# ReadCard.net
KiCad netlist of a schematic drawn in Altium Designer
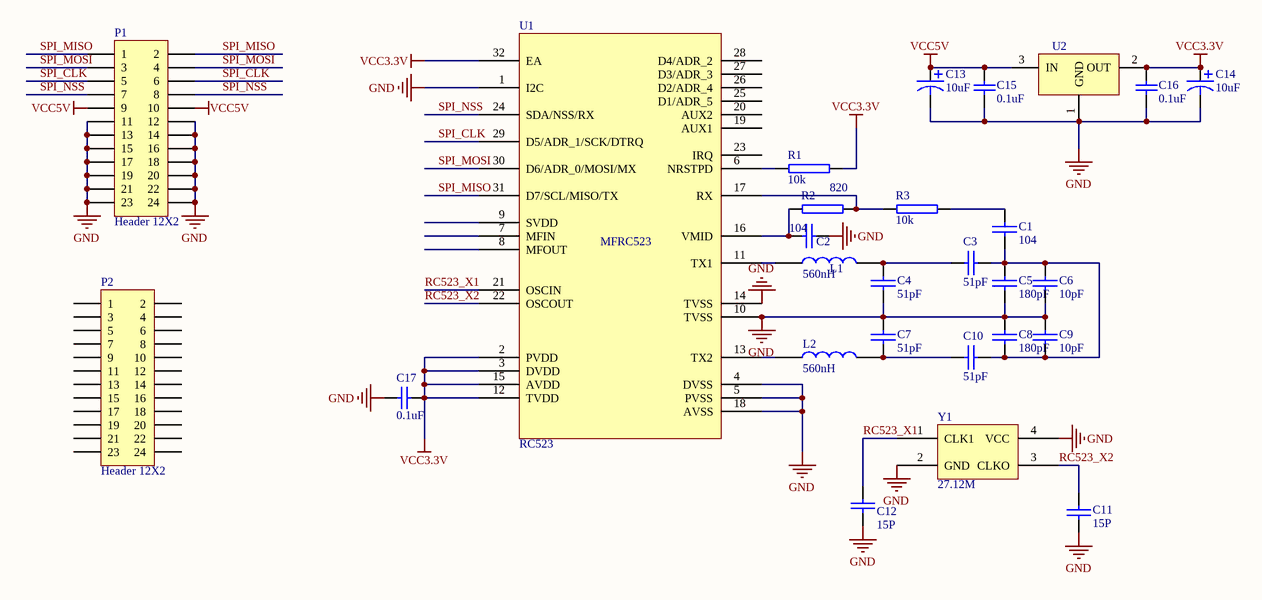
[diagram p0: ReadCard.SchDoc]

(export (version "E")
  (design (tool "Eeschema 10.0.6"))
  (components
    (comp (ref "C1")
      (value "104")
      (footprint "0603C")
      (description "Capacitor")
      (libsource (lib "*") (part "CAP"))
    )
    (comp (ref "C2")
      (value "104")
      (footprint "0603C")
      (description "Capacitor")
      (libsource (lib "*") (part "CAP"))
    )
    (comp (ref "C3")
      (value "51pF")
      (footprint "0603C")
      (description "Capacitor")
      (libsource (lib "*") (part "CAP"))
    )
    (comp (ref "C4")
      (value "51pF")
      (footprint "0603C")
      (description "Capacitor")
      (libsource (lib "*") (part "CAP"))
    )
    (comp (ref "C5")
      (value "180pF")
      (footprint "0603C")
      (description "Capacitor")
      (libsource (lib "*") (part "CAP"))
    )
    (comp (ref "C6")
      (value "10pF")
      (footprint "0603C")
      (description "Capacitor")
      (libsource (lib "*") (part "CAP"))
    )
    (comp (ref "C7")
      (value "51pF")
      (footprint "0603C")
      (description "Capacitor")
      (libsource (lib "*") (part "CAP"))
    )
    (comp (ref "C8")
      (value "180pF")
      (footprint "0603C")
      (description "Capacitor")
      (libsource (lib "*") (part "CAP"))
    )
    (comp (ref "C9")
      (value "10pF")
      (footprint "0603C")
      (description "Capacitor")
      (libsource (lib "*") (part "CAP"))
    )
    (comp (ref "C10")
      (value "51pF")
      (footprint "0603C")
      (description "Capacitor")
      (libsource (lib "*") (part "CAP"))
    )
    (comp (ref "C11")
      (value "15P")
      (footprint "0603c")
      (description "Capacitor")
      (libsource (lib "") (part "CAP_1"))
    )
    (comp (ref "C12")
      (value "15P")
      (footprint "0603C")
      (description "Capacitor")
      (libsource (lib "") (part "CAP_1"))
    )
    (comp (ref "C13")
      (value "10uF")
      (footprint "1206_C")
      (description "贴片电容，1206")
      (libsource (lib "MES-terminal") (part "CAPACITOR"))
    )
    (comp (ref "C14")
      (value "10uF")
      (footprint "1206_C")
      (description "贴片电容，1206")
      (libsource (lib "MES-terminal") (part "CAPACITOR"))
    )
    (comp (ref "C15")
      (value "0.1uF")
      (footprint "0603_C")
      (description "贴片电容，0603")
      (libsource (lib "stm8l052r8t6开发板") (part "Cap"))
    )
    (comp (ref "C16")
      (value "0.1uF")
      (footprint "0603_C")
      (description "贴片电容，0603")
      (libsource (lib "stm8l052r8t6开发板") (part "Cap"))
    )
    (comp (ref "C17")
      (value "0.1uF")
      (footprint "0603_C")
      (description "贴片电容，0603")
      (libsource (lib "stm8l052r8t6开发板") (part "Cap"))
    )
    (comp (ref "L1") (value "560nH") (footprint "0805r") (libsource (lib "*") (part "INDUCTOR1")))
    (comp (ref "L2") (value "560nH") (footprint "0805r") (libsource (lib "*") (part "INDUCTOR1")))
    (comp (ref "P1")
      (value "Header 12X2")
      (footprint "12x2_2.0mm")
      (description "Header, 12-Pin, Dual row, 2.0mm")
      (libsource (lib "Miscellaneous Connectors") (part "Header 12X2"))
    )
    (comp (ref "P2")
      (value "Header 12X2")
      (footprint "12x2_2.0mm")
      (description "Header, 12-Pin, Dual row, 2.0mm")
      (libsource (lib "Miscellaneous Connectors") (part "Header 12X2"))
    )
    (comp (ref "R1") (value "10k") (footprint "0603R") (libsource (lib "*") (part "RES2")))
    (comp (ref "R2") (value "820") (footprint "0603R") (libsource (lib "*") (part "RES2")))
    (comp (ref "R3") (value "10k") (footprint "0603R") (libsource (lib "*") (part "RES2")))
    (comp (ref "U1") (value "RC523") (footprint "rc522") (libsource (lib "wuqin0") (part "RC523")))
    (comp (ref "U2")
      (value "LM1117")
      (footprint "SOT-223")
      (libsource (lib "stm8l052r8t6开发板") (part "LM1117"))
    )
    (comp (ref "Y1") (value "27.12M") (footprint "27.12M_3225") (libsource (lib "lsb") (part "XTAL")))
  )
  (nets
    (net (code "1") (name "/RC523_X1") (class "Default")
      (node (ref "C12") (pin "2") (pinfunction "2_2") (pintype "passive"))
      (node (ref "U1") (pin "21") (pinfunction "OSCIN_21") (pintype "passive"))
      (node (ref "Y1") (pin "1") (pinfunction "CLK1_1") (pintype "passive"))
    )
    (net (code "2") (name "/RC523_X2") (class "Default")
      (node (ref "C11") (pin "2") (pinfunction "2_2") (pintype "passive"))
      (node (ref "U1") (pin "22") (pinfunction "OSCOUT_22") (pintype "passive"))
      (node (ref "Y1") (pin "3") (pinfunction "CLKO_3") (pintype "passive"))
    )
    (net (code "3") (name "/SPI_CLK") (class "Default")
      (node (ref "P1") (pin "5") (pinfunction "5_5") (pintype "passive"))
      (node (ref "P1") (pin "6") (pinfunction "6_6") (pintype "passive"))
      (node (ref "U1") (pin "29") (pinfunction "D5/ADR_1/SCK/DTRQ_29") (pintype "passive"))
    )
    (net (code "4") (name "/SPI_MISO") (class "Default")
      (node (ref "P1") (pin "1") (pinfunction "1_1") (pintype "passive"))
      (node (ref "P1") (pin "2") (pinfunction "2_2") (pintype "passive"))
      (node (ref "U1") (pin "31") (pinfunction "D7/SCL/MISO/TX_31") (pintype "passive"))
    )
    (net (code "5") (name "/SPI_MOSI") (class "Default")
      (node (ref "P1") (pin "3") (pinfunction "3_3") (pintype "passive"))
      (node (ref "P1") (pin "4") (pinfunction "4_4") (pintype "passive"))
      (node (ref "U1") (pin "30") (pinfunction "D6/ADR_0/MOSI/MX_30") (pintype "passive"))
    )
    (net (code "6") (name "/SPI_NSS") (class "Default")
      (node (ref "P1") (pin "7") (pinfunction "7_7") (pintype "passive"))
      (node (ref "P1") (pin "8") (pinfunction "8_8") (pintype "passive"))
      (node (ref "U1") (pin "24") (pinfunction "SDA/NSS/RX_24") (pintype "passive"))
    )
    (net (code "7") (name "GND") (class "Default")
      (node (ref "C11") (pin "1") (pinfunction "1_1") (pintype "passive"))
      (node (ref "C12") (pin "1") (pinfunction "1_1") (pintype "passive"))
      (node (ref "C13") (pin "2") (pinfunction "2_2") (pintype "passive"))
      (node (ref "C14") (pin "2") (pinfunction "2_2") (pintype "passive"))
      (node (ref "C15") (pin "2") (pinfunction "2_2") (pintype "passive"))
      (node (ref "C16") (pin "2") (pinfunction "2_2") (pintype "passive"))
      (node (ref "C17") (pin "1") (pinfunction "1_1") (pintype "passive"))
      (node (ref "C2") (pin "1") (pinfunction "1_1") (pintype "passive"))
      (node (ref "C4") (pin "2") (pinfunction "2_2") (pintype "passive"))
      (node (ref "C5") (pin "2") (pinfunction "2_2") (pintype "passive"))
      (node (ref "C6") (pin "2") (pinfunction "2_2") (pintype "passive"))
      (node (ref "C7") (pin "1") (pinfunction "1_1") (pintype "passive"))
      (node (ref "C8") (pin "1") (pinfunction "1_1") (pintype "passive"))
      (node (ref "C9") (pin "1") (pinfunction "1_1") (pintype "passive"))
      (node (ref "P1") (pin "11") (pinfunction "11_11") (pintype "passive"))
      (node (ref "P1") (pin "12") (pinfunction "12_12") (pintype "passive"))
      (node (ref "P1") (pin "13") (pinfunction "13_13") (pintype "passive"))
      (node (ref "P1") (pin "14") (pinfunction "14_14") (pintype "passive"))
      (node (ref "P1") (pin "15") (pinfunction "15_15") (pintype "passive"))
      (node (ref "P1") (pin "16") (pinfunction "16_16") (pintype "passive"))
      (node (ref "P1") (pin "17") (pinfunction "17_17") (pintype "passive"))
      (node (ref "P1") (pin "18") (pinfunction "18_18") (pintype "passive"))
      (node (ref "P1") (pin "19") (pinfunction "19_19") (pintype "passive"))
      (node (ref "P1") (pin "20") (pinfunction "20_20") (pintype "passive"))
      (node (ref "P1") (pin "21") (pinfunction "21_21") (pintype "passive"))
      (node (ref "P1") (pin "22") (pinfunction "22_22") (pintype "passive"))
      (node (ref "P1") (pin "23") (pinfunction "23_23") (pintype "passive"))
      (node (ref "P1") (pin "24") (pinfunction "24_24") (pintype "passive"))
      (node (ref "U1") (pin "1") (pinfunction "I2C_1") (pintype "passive"))
      (node (ref "U1") (pin "10") (pinfunction "TVSS_10") (pintype "passive"))
      (node (ref "U1") (pin "14") (pinfunction "TVSS_14") (pintype "passive"))
      (node (ref "U1") (pin "18") (pinfunction "AVSS_18") (pintype "passive"))
      (node (ref "U1") (pin "4") (pinfunction "DVSS_4") (pintype "passive"))
      (node (ref "U1") (pin "5") (pinfunction "PVSS_5") (pintype "passive"))
      (node (ref "U2") (pin "1") (pinfunction "GND_1") (pintype "passive"))
      (node (ref "Y1") (pin "2") (pinfunction "GND_2") (pintype "passive"))
      (node (ref "Y1") (pin "4") (pinfunction "VCC_4") (pintype "passive"))
    )
    (net (code "8") (name "Net-(C1-Pad1)") (class "Default")
      (node (ref "C1") (pin "1") (pinfunction "1_1") (pintype "passive"))
      (node (ref "R3") (pin "1") (pinfunction "1_1") (pintype "passive"))
    )
    (net (code "9") (name "Net-(C1-Pad2)") (class "Default")
      (node (ref "C1") (pin "2") (pinfunction "2_2") (pintype "passive"))
      (node (ref "C10") (pin "2") (pinfunction "2_2") (pintype "passive"))
      (node (ref "C3") (pin "2") (pinfunction "2_2") (pintype "passive"))
      (node (ref "C5") (pin "1") (pinfunction "1_1") (pintype "passive"))
      (node (ref "C6") (pin "1") (pinfunction "1_1") (pintype "passive"))
      (node (ref "C8") (pin "2") (pinfunction "2_2") (pintype "passive"))
      (node (ref "C9") (pin "2") (pinfunction "2_2") (pintype "passive"))
    )
    (net (code "10") (name "Net-(C3-Pad1)") (class "Default")
      (node (ref "C3") (pin "1") (pinfunction "1_1") (pintype "passive"))
      (node (ref "C4") (pin "1") (pinfunction "1_1") (pintype "passive"))
      (node (ref "L1") (pin "2") (pinfunction "2_2") (pintype "passive"))
    )
    (net (code "11") (name "Net-(C10-Pad1)") (class "Default")
      (node (ref "C10") (pin "1") (pinfunction "1_1") (pintype "passive"))
      (node (ref "C7") (pin "2") (pinfunction "2_2") (pintype "passive"))
      (node (ref "L2") (pin "2") (pinfunction "2_2") (pintype "passive"))
    )
    (net (code "12") (name "Net-(U1-NRSTPD)") (class "Default")
      (node (ref "R1") (pin "1") (pinfunction "1_1") (pintype "passive"))
      (node (ref "U1") (pin "6") (pinfunction "NRSTPD_6") (pintype "passive"))
    )
    (net (code "13") (name "Net-(U1-RX)") (class "Default")
      (node (ref "R2") (pin "1") (pinfunction "1_1") (pintype "passive"))
      (node (ref "R3") (pin "2") (pinfunction "2_2") (pintype "passive"))
      (node (ref "U1") (pin "17") (pinfunction "RX_17") (pintype "passive"))
    )
    (net (code "14") (name "Net-(U1-TX1)") (class "Default")
      (node (ref "L1") (pin "1") (pinfunction "1_1") (pintype "passive"))
      (node (ref "U1") (pin "11") (pinfunction "TX1_11") (pintype "passive"))
    )
    (net (code "15") (name "Net-(U1-TX2)") (class "Default")
      (node (ref "L2") (pin "1") (pinfunction "1_1") (pintype "passive"))
      (node (ref "U1") (pin "13") (pinfunction "TX2_13") (pintype "passive"))
    )
    (net (code "16") (name "Net-(U1-VMID)") (class "Default")
      (node (ref "C2") (pin "2") (pinfunction "2_2") (pintype "passive"))
      (node (ref "R2") (pin "2") (pinfunction "2_2") (pintype "passive"))
      (node (ref "U1") (pin "16") (pinfunction "VMID_16") (pintype "passive"))
    )
    (net (code "17") (name "VCC3.3V") (class "Default")
      (node (ref "C14") (pin "1") (pinfunction "1_1") (pintype "passive"))
      (node (ref "C16") (pin "1") (pinfunction "1_1") (pintype "passive"))
      (node (ref "C17") (pin "2") (pinfunction "2_2") (pintype "passive"))
      (node (ref "R1") (pin "2") (pinfunction "2_2") (pintype "passive"))
      (node (ref "U1") (pin "12") (pinfunction "TVDD_12") (pintype "passive"))
      (node (ref "U1") (pin "15") (pinfunction "AVDD_15") (pintype "passive"))
      (node (ref "U1") (pin "2") (pinfunction "PVDD_2") (pintype "passive"))
      (node (ref "U1") (pin "3") (pinfunction "DVDD_3") (pintype "passive"))
      (node (ref "U1") (pin "32") (pinfunction "EA_32") (pintype "passive"))
      (node (ref "U2") (pin "2") (pinfunction "OUT_2") (pintype "passive"))
    )
    (net (code "18") (name "VCC5V") (class "Default")
      (node (ref "C13") (pin "1") (pinfunction "1_1") (pintype "passive"))
      (node (ref "C15") (pin "1") (pinfunction "1_1") (pintype "passive"))
      (node (ref "P1") (pin "10") (pinfunction "10_10") (pintype "passive"))
      (node (ref "P1") (pin "9") (pinfunction "9_9") (pintype "passive"))
      (node (ref "U2") (pin "3") (pinfunction "IN_3") (pintype "passive"))
    )
    (net (code "19") (name "unconnected-(P2-Pad1)") (class "Default")
      (node (ref "P2") (pin "1") (pinfunction "1_1") (pintype "passive"))
    )
    (net (code "20") (name "unconnected-(P2-Pad2)") (class "Default")
      (node (ref "P2") (pin "2") (pinfunction "2_2") (pintype "passive"))
    )
    (net (code "21") (name "unconnected-(P2-Pad3)") (class "Default")
      (node (ref "P2") (pin "3") (pinfunction "3_3") (pintype "passive"))
    )
    (net (code "22") (name "unconnected-(P2-Pad4)") (class "Default")
      (node (ref "P2") (pin "4") (pinfunction "4_4") (pintype "passive"))
    )
    (net (code "23") (name "unconnected-(P2-Pad5)") (class "Default")
      (node (ref "P2") (pin "5") (pinfunction "5_5") (pintype "passive"))
    )
    (net (code "24") (name "unconnected-(P2-Pad6)") (class "Default")
      (node (ref "P2") (pin "6") (pinfunction "6_6") (pintype "passive"))
    )
    (net (code "25") (name "unconnected-(P2-Pad7)") (class "Default")
      (node (ref "P2") (pin "7") (pinfunction "7_7") (pintype "passive"))
    )
    (net (code "26") (name "unconnected-(P2-Pad8)") (class "Default")
      (node (ref "P2") (pin "8") (pinfunction "8_8") (pintype "passive"))
    )
    (net (code "27") (name "unconnected-(P2-Pad9)") (class "Default")
      (node (ref "P2") (pin "9") (pinfunction "9_9") (pintype "passive"))
    )
    (net (code "28") (name "unconnected-(P2-Pad10)") (class "Default")
      (node (ref "P2") (pin "10") (pinfunction "10_10") (pintype "passive"))
    )
    (net (code "29") (name "unconnected-(P2-Pad11)") (class "Default")
      (node (ref "P2") (pin "11") (pinfunction "11_11") (pintype "passive"))
    )
    (net (code "30") (name "unconnected-(P2-Pad12)") (class "Default")
      (node (ref "P2") (pin "12") (pinfunction "12_12") (pintype "passive"))
    )
    (net (code "31") (name "unconnected-(P2-Pad13)") (class "Default")
      (node (ref "P2") (pin "13") (pinfunction "13_13") (pintype "passive"))
    )
    (net (code "32") (name "unconnected-(P2-Pad14)") (class "Default")
      (node (ref "P2") (pin "14") (pinfunction "14_14") (pintype "passive"))
    )
    (net (code "33") (name "unconnected-(P2-Pad15)") (class "Default")
      (node (ref "P2") (pin "15") (pinfunction "15_15") (pintype "passive"))
    )
    (net (code "34") (name "unconnected-(P2-Pad16)") (class "Default")
      (node (ref "P2") (pin "16") (pinfunction "16_16") (pintype "passive"))
    )
    (net (code "35") (name "unconnected-(P2-Pad17)") (class "Default")
      (node (ref "P2") (pin "17") (pinfunction "17_17") (pintype "passive"))
    )
    (net (code "36") (name "unconnected-(P2-Pad18)") (class "Default")
      (node (ref "P2") (pin "18") (pinfunction "18_18") (pintype "passive"))
    )
    (net (code "37") (name "unconnected-(P2-Pad19)") (class "Default")
      (node (ref "P2") (pin "19") (pinfunction "19_19") (pintype "passive"))
    )
    (net (code "38") (name "unconnected-(P2-Pad20)") (class "Default")
      (node (ref "P2") (pin "20") (pinfunction "20_20") (pintype "passive"))
    )
    (net (code "39") (name "unconnected-(P2-Pad21)") (class "Default")
      (node (ref "P2") (pin "21") (pinfunction "21_21") (pintype "passive"))
    )
    (net (code "40") (name "unconnected-(P2-Pad22)") (class "Default")
      (node (ref "P2") (pin "22") (pinfunction "22_22") (pintype "passive"))
    )
    (net (code "41") (name "unconnected-(P2-Pad23)") (class "Default")
      (node (ref "P2") (pin "23") (pinfunction "23_23") (pintype "passive"))
    )
    (net (code "42") (name "unconnected-(P2-Pad24)") (class "Default")
      (node (ref "P2") (pin "24") (pinfunction "24_24") (pintype "passive"))
    )
    (net (code "43") (name "unconnected-(U1-AUX1-Pad19)") (class "Default")
      (node (ref "U1") (pin "19") (pinfunction "AUX1_19") (pintype "passive"))
    )
    (net (code "44") (name "unconnected-(U1-AUX2-Pad20)") (class "Default")
      (node (ref "U1") (pin "20") (pinfunction "AUX2_20") (pintype "passive"))
    )
    (net (code "45") (name "unconnected-(U1-D1{slash}ADR_5-Pad25)") (class "Default")
      (node (ref "U1") (pin "25") (pinfunction "D1/ADR_5_25") (pintype "passive"))
    )
    (net (code "46") (name "unconnected-(U1-D2{slash}ADR_4-Pad26)") (class "Default")
      (node (ref "U1") (pin "26") (pinfunction "D2/ADR_4_26") (pintype "passive"))
    )
    (net (code "47") (name "unconnected-(U1-D3{slash}ADR_3-Pad27)") (class "Default")
      (node (ref "U1") (pin "27") (pinfunction "D3/ADR_3_27") (pintype "passive"))
    )
    (net (code "48") (name "unconnected-(U1-D4{slash}ADR_2-Pad28)") (class "Default")
      (node (ref "U1") (pin "28") (pinfunction "D4/ADR_2_28") (pintype "passive"))
    )
    (net (code "49") (name "unconnected-(U1-IRQ-Pad23)") (class "Default")
      (node (ref "U1") (pin "23") (pinfunction "IRQ_23") (pintype "passive"))
    )
    (net (code "50") (name "unconnected-(U1-MFIN-Pad7)") (class "Default")
      (node (ref "U1") (pin "7") (pinfunction "MFIN_7") (pintype "passive"))
    )
    (net (code "51") (name "unconnected-(U1-MFOUT-Pad8)") (class "Default")
      (node (ref "U1") (pin "8") (pinfunction "MFOUT_8") (pintype "passive"))
    )
    (net (code "52") (name "unconnected-(U1-SVDD-Pad9)") (class "Default")
      (node (ref "U1") (pin "9") (pinfunction "SVDD_9") (pintype "passive"))
    )
  )
)
